# FMC_connector.net
KiCad netlist of a schematic drawn in Altium Designer
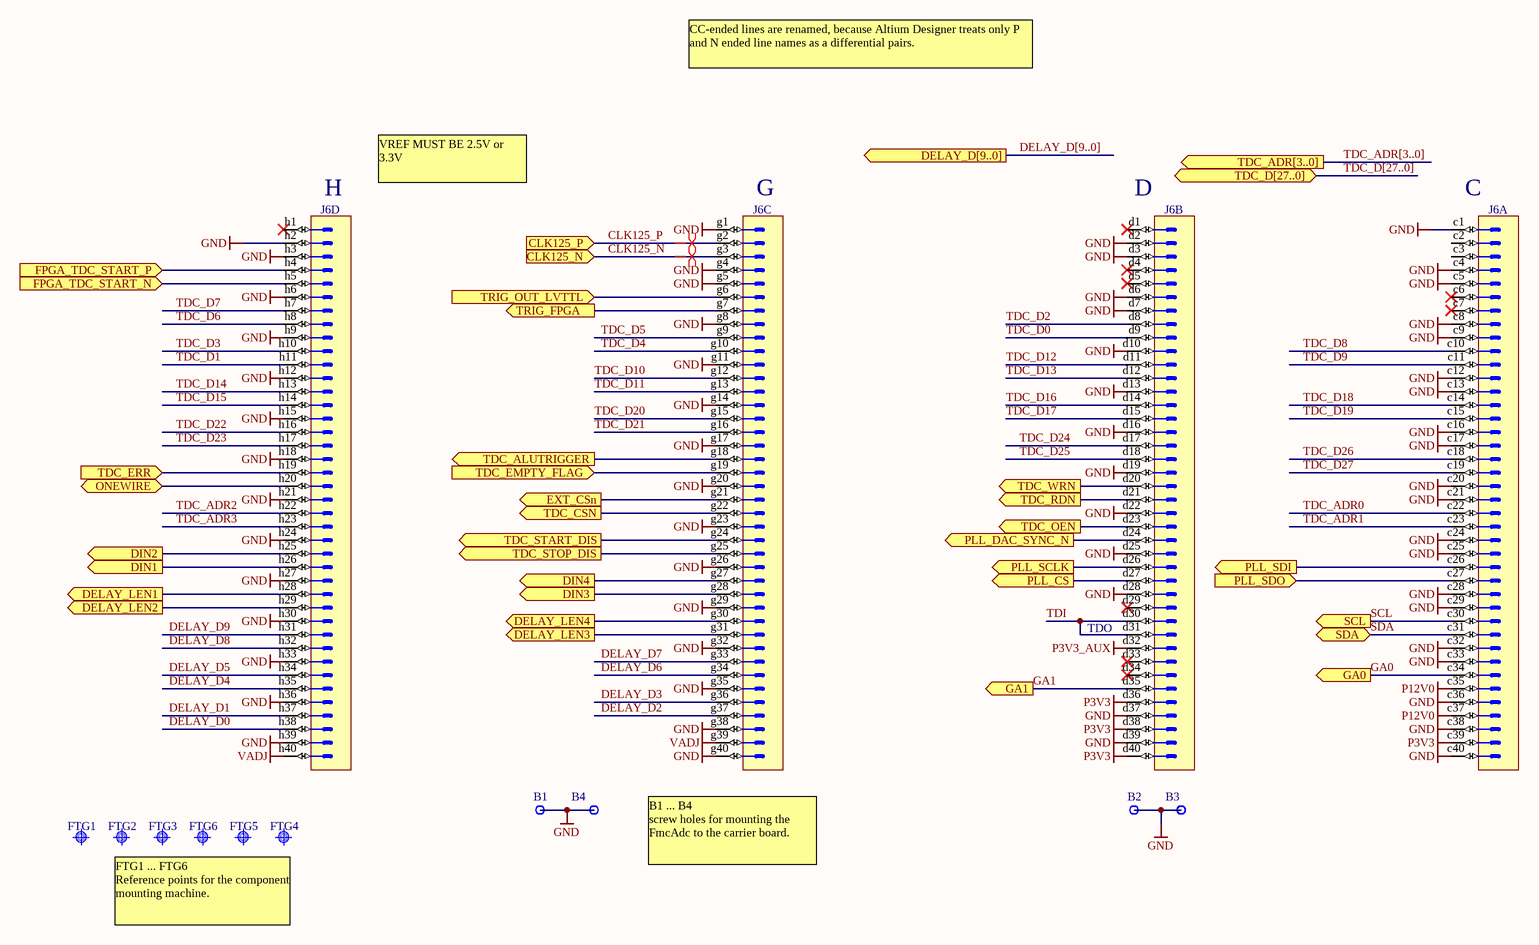
[diagram p0: FMC connector.SchDoc]

(export (version "E")
  (design (tool "Eeschema 10.0.6"))
  (components
    (comp (ref "B1")
      (value "Plated Hole")
      (footprint "MTG300_600")
      (description "Single Terminal Socket")
      (fields (field (name "PART NUMBER") "PLATED_HOLE3.0_PAD6.0") (field (name "AUTHOR") "CERN DEM JLC"))
      (libsource (lib "Eletro-mechanical") (part "Single Terminal Socket"))
    )
    (comp (ref "B2")
      (value "Plated Hole")
      (footprint "MTG300_600")
      (description "Single Terminal Socket")
      (fields (field (name "PART NUMBER") "PLATED_HOLE3.0_PAD6.0") (field (name "AUTHOR") "CERN DEM JLC"))
      (libsource (lib "Eletro-mechanical") (part "Single Terminal Socket"))
    )
    (comp (ref "B3")
      (value "Plated Hole")
      (footprint "MTG300_600")
      (description "Single Terminal Socket")
      (fields (field (name "PART NUMBER") "PLATED_HOLE3.0_PAD6.0") (field (name "AUTHOR") "CERN DEM JLC"))
      (libsource (lib "Eletro-mechanical") (part "Single Terminal Socket"))
    )
    (comp (ref "B4")
      (value "Plated Hole")
      (footprint "MTG300_600")
      (description "Single Terminal Socket")
      (fields (field (name "PART NUMBER") "PLATED_HOLE3.0_PAD6.0") (field (name "AUTHOR") "CERN DEM JLC"))
      (libsource (lib "Eletro-mechanical") (part "Single Terminal Socket"))
    )
    (comp (ref "FTG1")
      (value "Use only in PCB")
      (footprint "FIDUCIAL_TOP_S100-200")
      (description "Fiducial Target")
      (fields (field (name "PART NUMBER") "FIDUCIAL_TARGET_S100-200") (field (name "AUTHOR") "CERN DEM JLC"))
      (libsource (lib "Eletro-mechanical") (part "Fiducial Target"))
    )
    (comp (ref "FTG2")
      (value "Use only in PCB")
      (footprint "FIDUCIAL_TOP_S100-200")
      (description "Fiducial Target")
      (fields (field (name "PART NUMBER") "FIDUCIAL_TARGET_S100-200") (field (name "AUTHOR") "CERN DEM JLC"))
      (libsource (lib "Eletro-mechanical") (part "Fiducial Target"))
    )
    (comp (ref "FTG3")
      (value "Use only in PCB")
      (footprint "FIDUCIAL_TOP_S100-200")
      (description "Fiducial Target")
      (fields (field (name "PART NUMBER") "FIDUCIAL_TARGET_S100-200") (field (name "AUTHOR") "CERN DEM JLC"))
      (libsource (lib "Eletro-mechanical") (part "Fiducial Target"))
    )
    (comp (ref "FTG4")
      (value "Use only in PCB")
      (footprint "FIDUCIAL_TOP_S100-200")
      (description "Fiducial Target")
      (fields (field (name "PART NUMBER") "FIDUCIAL_TARGET_S100-200") (field (name "AUTHOR") "CERN DEM JLC"))
      (libsource (lib "Eletro-mechanical") (part "Fiducial Target"))
    )
    (comp (ref "FTG5")
      (value "Use only in PCB")
      (footprint "FIDUCIAL_TOP_S100-200")
      (description "Fiducial Target")
      (fields (field (name "PART NUMBER") "FIDUCIAL_TARGET_S100-200") (field (name "AUTHOR") "CERN DEM JLC"))
      (libsource (lib "Eletro-mechanical") (part "Fiducial Target"))
    )
    (comp (ref "FTG6")
      (value "Use only in PCB")
      (footprint "FIDUCIAL_TOP_S100-200")
      (description "Fiducial Target")
      (fields (field (name "PART NUMBER") "FIDUCIAL_TARGET_S100-200") (field (name "AUTHOR") "CERN DEM JLC"))
      (libsource (lib "Eletro-mechanical") (part "Fiducial Target"))
    )
    (comp (ref "J6")
      (value "VITA 57")
      (footprint "SAMTEC_ASP-127797-01")
      (description "Connector VITA 57, 160 Male contacts in 4 row cdgh")
      (fields
        (field (name "PART NUMBER") "SAMTEC_ASP-127797-01")
        (field (name "MANUFACTURER") "SAMTEC")
        (field (name "AUTHOR") "CERN DEM JLC")
      )
      (libsource (lib "Connectors") (part "Connector VITA 57 160 Male (cdgh)"))
    )
  )
  (nets
    (net (code "1") (name "/CLK125_N") (class "Default")
      (node (ref "J6") (pin "g3") (pinfunction "g3_g3") (pintype "bidirectional"))
    )
    (net (code "2") (name "/CLK125_P") (class "Default")
      (node (ref "J6") (pin "g2") (pinfunction "g2_g2") (pintype "bidirectional"))
    )
    (net (code "3") (name "/DELAY_D0") (class "Default")
      (node (ref "J6") (pin "h38") (pinfunction "h38_h38") (pintype "bidirectional"))
    )
    (net (code "4") (name "/DELAY_D1") (class "Default")
      (node (ref "J6") (pin "h37") (pinfunction "h37_h37") (pintype "bidirectional"))
    )
    (net (code "5") (name "/DELAY_D2") (class "Default")
      (node (ref "J6") (pin "g37") (pinfunction "g37_g37") (pintype "bidirectional"))
    )
    (net (code "6") (name "/DELAY_D3") (class "Default")
      (node (ref "J6") (pin "g36") (pinfunction "g36_g36") (pintype "bidirectional"))
    )
    (net (code "7") (name "/DELAY_D4") (class "Default")
      (node (ref "J6") (pin "h35") (pinfunction "h35_h35") (pintype "bidirectional"))
    )
    (net (code "8") (name "/DELAY_D5") (class "Default")
      (node (ref "J6") (pin "h34") (pinfunction "h34_h34") (pintype "bidirectional"))
    )
    (net (code "9") (name "/DELAY_D6") (class "Default")
      (node (ref "J6") (pin "g34") (pinfunction "g34_g34") (pintype "bidirectional"))
    )
    (net (code "10") (name "/DELAY_D7") (class "Default")
      (node (ref "J6") (pin "g33") (pinfunction "g33_g33") (pintype "bidirectional"))
    )
    (net (code "11") (name "/DELAY_D8") (class "Default")
      (node (ref "J6") (pin "h32") (pinfunction "h32_h32") (pintype "bidirectional"))
    )
    (net (code "12") (name "/DELAY_D9") (class "Default")
      (node (ref "J6") (pin "h31") (pinfunction "h31_h31") (pintype "bidirectional"))
    )
    (net (code "14") (name "/DELAY_LEN1") (class "Default")
      (node (ref "J6") (pin "h28") (pinfunction "h28_h28") (pintype "bidirectional"))
    )
    (net (code "15") (name "/DELAY_LEN2") (class "Default")
      (node (ref "J6") (pin "h29") (pinfunction "h29_h29") (pintype "bidirectional"))
    )
    (net (code "16") (name "/DELAY_LEN3") (class "Default")
      (node (ref "J6") (pin "g31") (pinfunction "g31_g31") (pintype "bidirectional"))
    )
    (net (code "17") (name "/DELAY_LEN4") (class "Default")
      (node (ref "J6") (pin "g30") (pinfunction "g30_g30") (pintype "bidirectional"))
    )
    (net (code "18") (name "/DIN1") (class "Default")
      (node (ref "J6") (pin "h26") (pinfunction "h26_h26") (pintype "bidirectional"))
    )
    (net (code "19") (name "/DIN2") (class "Default")
      (node (ref "J6") (pin "h25") (pinfunction "h25_h25") (pintype "bidirectional"))
    )
    (net (code "20") (name "/DIN3") (class "Default")
      (node (ref "J6") (pin "g28") (pinfunction "g28_g28") (pintype "bidirectional"))
    )
    (net (code "21") (name "/DIN4") (class "Default")
      (node (ref "J6") (pin "g27") (pinfunction "g27_g27") (pintype "bidirectional"))
    )
    (net (code "22") (name "/EXT_CSn") (class "Default")
      (node (ref "J6") (pin "g21") (pinfunction "g21_g21") (pintype "bidirectional"))
    )
    (net (code "23") (name "/FPGA_TDC_START_N") (class "Default")
      (node (ref "J6") (pin "h5") (pinfunction "h5_h5") (pintype "bidirectional"))
    )
    (net (code "24") (name "/FPGA_TDC_START_P") (class "Default")
      (node (ref "J6") (pin "h4") (pinfunction "h4_h4") (pintype "bidirectional"))
    )
    (net (code "25") (name "/GA0") (class "Default")
      (node (ref "J6") (pin "c34") (pinfunction "c34_c34") (pintype "bidirectional"))
    )
    (net (code "26") (name "/GA1") (class "Default")
      (node (ref "J6") (pin "d35") (pinfunction "d35_d35") (pintype "bidirectional"))
    )
    (net (code "27") (name "/ONEWIRE") (class "Default")
      (node (ref "J6") (pin "h20") (pinfunction "h20_h20") (pintype "bidirectional"))
    )
    (net (code "28") (name "/PLL_CS") (class "Default")
      (node (ref "J6") (pin "d27") (pinfunction "d27_d27") (pintype "bidirectional"))
    )
    (net (code "29") (name "/PLL_DAC_SYNC_N") (class "Default")
      (node (ref "J6") (pin "d24") (pinfunction "d24_d24") (pintype "bidirectional"))
    )
    (net (code "30") (name "/PLL_SCLK") (class "Default")
      (node (ref "J6") (pin "d26") (pinfunction "d26_d26") (pintype "bidirectional"))
    )
    (net (code "31") (name "/PLL_SDI") (class "Default")
      (node (ref "J6") (pin "c26") (pinfunction "c26_c26") (pintype "bidirectional"))
    )
    (net (code "32") (name "/PLL_SDO") (class "Default")
      (node (ref "J6") (pin "c27") (pinfunction "c27_c27") (pintype "bidirectional"))
    )
    (net (code "33") (name "/SCL") (class "Default")
      (node (ref "J6") (pin "c30") (pinfunction "c30_c30") (pintype "bidirectional"))
    )
    (net (code "34") (name "/SDA") (class "Default")
      (node (ref "J6") (pin "c31") (pinfunction "c31_c31") (pintype "bidirectional"))
    )
    (net (code "35") (name "/TDC_ADR0") (class "Default")
      (node (ref "J6") (pin "c22") (pinfunction "c22_c22") (pintype "bidirectional"))
    )
    (net (code "36") (name "/TDC_ADR1") (class "Default")
      (node (ref "J6") (pin "c23") (pinfunction "c23_c23") (pintype "bidirectional"))
    )
    (net (code "37") (name "/TDC_ADR2") (class "Default")
      (node (ref "J6") (pin "h22") (pinfunction "h22_h22") (pintype "bidirectional"))
    )
    (net (code "38") (name "/TDC_ADR3") (class "Default")
      (node (ref "J6") (pin "h23") (pinfunction "h23_h23") (pintype "bidirectional"))
    )
    (net (code "40") (name "/TDC_ALUTRIGGER") (class "Default")
      (node (ref "J6") (pin "g18") (pinfunction "g18_g18") (pintype "bidirectional"))
    )
    (net (code "41") (name "/TDC_CSN") (class "Default")
      (node (ref "J6") (pin "g22") (pinfunction "g22_g22") (pintype "bidirectional"))
    )
    (net (code "42") (name "/TDC_D0") (class "Default")
      (node (ref "J6") (pin "d9") (pinfunction "d9_d9") (pintype "bidirectional"))
    )
    (net (code "43") (name "/TDC_D1") (class "Default")
      (node (ref "J6") (pin "h11") (pinfunction "h11_h11") (pintype "bidirectional"))
    )
    (net (code "44") (name "/TDC_D2") (class "Default")
      (node (ref "J6") (pin "d8") (pinfunction "d8_d8") (pintype "bidirectional"))
    )
    (net (code "45") (name "/TDC_D3") (class "Default")
      (node (ref "J6") (pin "h10") (pinfunction "h10_h10") (pintype "bidirectional"))
    )
    (net (code "46") (name "/TDC_D4") (class "Default")
      (node (ref "J6") (pin "g10") (pinfunction "g10_g10") (pintype "bidirectional"))
    )
    (net (code "47") (name "/TDC_D5") (class "Default")
      (node (ref "J6") (pin "g9") (pinfunction "g9_g9") (pintype "bidirectional"))
    )
    (net (code "48") (name "/TDC_D6") (class "Default")
      (node (ref "J6") (pin "h8") (pinfunction "h8_h8") (pintype "bidirectional"))
    )
    (net (code "49") (name "/TDC_D7") (class "Default")
      (node (ref "J6") (pin "h7") (pinfunction "h7_h7") (pintype "bidirectional"))
    )
    (net (code "50") (name "/TDC_D8") (class "Default")
      (node (ref "J6") (pin "c10") (pinfunction "c10_c10") (pintype "bidirectional"))
    )
    (net (code "51") (name "/TDC_D9") (class "Default")
      (node (ref "J6") (pin "c11") (pinfunction "c11_c11") (pintype "bidirectional"))
    )
    (net (code "52") (name "/TDC_D10") (class "Default")
      (node (ref "J6") (pin "g12") (pinfunction "g12_g12") (pintype "bidirectional"))
    )
    (net (code "53") (name "/TDC_D11") (class "Default")
      (node (ref "J6") (pin "g13") (pinfunction "g13_g13") (pintype "bidirectional"))
    )
    (net (code "54") (name "/TDC_D12") (class "Default")
      (node (ref "J6") (pin "d11") (pinfunction "d11_d11") (pintype "bidirectional"))
    )
    (net (code "55") (name "/TDC_D13") (class "Default")
      (node (ref "J6") (pin "d12") (pinfunction "d12_d12") (pintype "bidirectional"))
    )
    (net (code "56") (name "/TDC_D14") (class "Default")
      (node (ref "J6") (pin "h13") (pinfunction "h13_h13") (pintype "bidirectional"))
    )
    (net (code "57") (name "/TDC_D15") (class "Default")
      (node (ref "J6") (pin "h14") (pinfunction "h14_h14") (pintype "bidirectional"))
    )
    (net (code "58") (name "/TDC_D16") (class "Default")
      (node (ref "J6") (pin "d14") (pinfunction "d14_d14") (pintype "bidirectional"))
    )
    (net (code "59") (name "/TDC_D17") (class "Default")
      (node (ref "J6") (pin "d15") (pinfunction "d15_d15") (pintype "bidirectional"))
    )
    (net (code "60") (name "/TDC_D18") (class "Default")
      (node (ref "J6") (pin "c14") (pinfunction "c14_c14") (pintype "bidirectional"))
    )
    (net (code "61") (name "/TDC_D19") (class "Default")
      (node (ref "J6") (pin "c15") (pinfunction "c15_c15") (pintype "bidirectional"))
    )
    (net (code "62") (name "/TDC_D20") (class "Default")
      (node (ref "J6") (pin "g15") (pinfunction "g15_g15") (pintype "bidirectional"))
    )
    (net (code "63") (name "/TDC_D21") (class "Default")
      (node (ref "J6") (pin "g16") (pinfunction "g16_g16") (pintype "bidirectional"))
    )
    (net (code "64") (name "/TDC_D22") (class "Default")
      (node (ref "J6") (pin "h16") (pinfunction "h16_h16") (pintype "bidirectional"))
    )
    (net (code "65") (name "/TDC_D23") (class "Default")
      (node (ref "J6") (pin "h17") (pinfunction "h17_h17") (pintype "bidirectional"))
    )
    (net (code "66") (name "/TDC_D24") (class "Default")
      (node (ref "J6") (pin "d17") (pinfunction "d17_d17") (pintype "bidirectional"))
    )
    (net (code "67") (name "/TDC_D25") (class "Default")
      (node (ref "J6") (pin "d18") (pinfunction "d18_d18") (pintype "bidirectional"))
    )
    (net (code "68") (name "/TDC_D26") (class "Default")
      (node (ref "J6") (pin "c18") (pinfunction "c18_c18") (pintype "bidirectional"))
    )
    (net (code "69") (name "/TDC_D27") (class "Default")
      (node (ref "J6") (pin "c19") (pinfunction "c19_c19") (pintype "bidirectional"))
    )
    (net (code "71") (name "/TDC_EMPTY_FLAG") (class "Default")
      (node (ref "J6") (pin "g19") (pinfunction "g19_g19") (pintype "bidirectional"))
    )
    (net (code "72") (name "/TDC_ERR") (class "Default")
      (node (ref "J6") (pin "h19") (pinfunction "h19_h19") (pintype "bidirectional"))
    )
    (net (code "73") (name "/TDC_OEN") (class "Default")
      (node (ref "J6") (pin "d23") (pinfunction "d23_d23") (pintype "bidirectional"))
    )
    (net (code "74") (name "/TDC_RDN") (class "Default")
      (node (ref "J6") (pin "d21") (pinfunction "d21_d21") (pintype "bidirectional"))
    )
    (net (code "75") (name "/TDC_START_DIS") (class "Default")
      (node (ref "J6") (pin "g24") (pinfunction "g24_g24") (pintype "bidirectional"))
    )
    (net (code "76") (name "/TDC_STOP_DIS") (class "Default")
      (node (ref "J6") (pin "g25") (pinfunction "g25_g25") (pintype "bidirectional"))
    )
    (net (code "77") (name "/TDC_WRN") (class "Default")
      (node (ref "J6") (pin "d20") (pinfunction "d20_d20") (pintype "bidirectional"))
    )
    (net (code "78") (name "/TDI") (class "Default")
      (node (ref "J6") (pin "d30") (pinfunction "d30_d30") (pintype "bidirectional"))
      (node (ref "J6") (pin "d31") (pinfunction "d31_d31") (pintype "bidirectional"))
    )
    (net (code "79") (name "/TRIG_FPGA") (class "Default")
      (node (ref "J6") (pin "g7") (pinfunction "g7_g7") (pintype "bidirectional"))
    )
    (net (code "80") (name "/TRIG_OUT_LVTTL") (class "Default")
      (node (ref "J6") (pin "g6") (pinfunction "g6_g6") (pintype "bidirectional"))
    )
    (net (code "81") (name "GND") (class "Default")
      (node (ref "B1") (pin "1") (pinfunction "1_1") (pintype "bidirectional"))
      (node (ref "B2") (pin "1") (pinfunction "1_1") (pintype "bidirectional"))
      (node (ref "B3") (pin "1") (pinfunction "1_1") (pintype "bidirectional"))
      (node (ref "B4") (pin "1") (pinfunction "1_1") (pintype "bidirectional"))
      (node (ref "J6") (pin "c1") (pinfunction "c1_c1") (pintype "bidirectional"))
      (node (ref "J6") (pin "c12") (pinfunction "c12_c12") (pintype "bidirectional"))
      (node (ref "J6") (pin "c13") (pinfunction "c13_c13") (pintype "bidirectional"))
      (node (ref "J6") (pin "c16") (pinfunction "c16_c16") (pintype "bidirectional"))
      (node (ref "J6") (pin "c17") (pinfunction "c17_c17") (pintype "bidirectional"))
      (node (ref "J6") (pin "c20") (pinfunction "c20_c20") (pintype "bidirectional"))
      (node (ref "J6") (pin "c21") (pinfunction "c21_c21") (pintype "bidirectional"))
      (node (ref "J6") (pin "c24") (pinfunction "c24_c24") (pintype "bidirectional"))
      (node (ref "J6") (pin "c25") (pinfunction "c25_c25") (pintype "bidirectional"))
      (node (ref "J6") (pin "c28") (pinfunction "c28_c28") (pintype "bidirectional"))
      (node (ref "J6") (pin "c29") (pinfunction "c29_c29") (pintype "bidirectional"))
      (node (ref "J6") (pin "c32") (pinfunction "c32_c32") (pintype "bidirectional"))
      (node (ref "J6") (pin "c33") (pinfunction "c33_c33") (pintype "bidirectional"))
      (node (ref "J6") (pin "c36") (pinfunction "c36_c36") (pintype "bidirectional"))
      (node (ref "J6") (pin "c38") (pinfunction "c38_c38") (pintype "bidirectional"))
      (node (ref "J6") (pin "c4") (pinfunction "c4_c4") (pintype "bidirectional"))
      (node (ref "J6") (pin "c40") (pinfunction "c40_c40") (pintype "bidirectional"))
      (node (ref "J6") (pin "c5") (pinfunction "c5_c5") (pintype "bidirectional"))
      (node (ref "J6") (pin "c8") (pinfunction "c8_c8") (pintype "bidirectional"))
      (node (ref "J6") (pin "c9") (pinfunction "c9_c9") (pintype "bidirectional"))
      (node (ref "J6") (pin "d10") (pinfunction "d10_d10") (pintype "bidirectional"))
      (node (ref "J6") (pin "d13") (pinfunction "d13_d13") (pintype "bidirectional"))
      (node (ref "J6") (pin "d16") (pinfunction "d16_d16") (pintype "bidirectional"))
      (node (ref "J6") (pin "d19") (pinfunction "d19_d19") (pintype "bidirectional"))
      (node (ref "J6") (pin "d2") (pinfunction "d2_d2") (pintype "bidirectional"))
      (node (ref "J6") (pin "d22") (pinfunction "d22_d22") (pintype "bidirectional"))
      (node (ref "J6") (pin "d25") (pinfunction "d25_d25") (pintype "bidirectional"))
      (node (ref "J6") (pin "d28") (pinfunction "d28_d28") (pintype "bidirectional"))
      (node (ref "J6") (pin "d3") (pinfunction "d3_d3") (pintype "bidirectional"))
      (node (ref "J6") (pin "d37") (pinfunction "d37_d37") (pintype "bidirectional"))
      (node (ref "J6") (pin "d39") (pinfunction "d39_d39") (pintype "bidirectional"))
      (node (ref "J6") (pin "d6") (pinfunction "d6_d6") (pintype "bidirectional"))
      (node (ref "J6") (pin "d7") (pinfunction "d7_d7") (pintype "bidirectional"))
      (node (ref "J6") (pin "g1") (pinfunction "g1_g1") (pintype "bidirectional"))
      (node (ref "J6") (pin "g11") (pinfunction "g11_g11") (pintype "bidirectional"))
      (node (ref "J6") (pin "g14") (pinfunction "g14_g14") (pintype "bidirectional"))
      (node (ref "J6") (pin "g17") (pinfunction "g17_g17") (pintype "bidirectional"))
      (node (ref "J6") (pin "g20") (pinfunction "g20_g20") (pintype "bidirectional"))
      (node (ref "J6") (pin "g23") (pinfunction "g23_g23") (pintype "bidirectional"))
      (node (ref "J6") (pin "g26") (pinfunction "g26_g26") (pintype "bidirectional"))
      (node (ref "J6") (pin "g29") (pinfunction "g29_g29") (pintype "bidirectional"))
      (node (ref "J6") (pin "g32") (pinfunction "g32_g32") (pintype "bidirectional"))
      (node (ref "J6") (pin "g35") (pinfunction "g35_g35") (pintype "bidirectional"))
      (node (ref "J6") (pin "g38") (pinfunction "g38_g38") (pintype "bidirectional"))
      (node (ref "J6") (pin "g4") (pinfunction "g4_g4") (pintype "bidirectional"))
      (node (ref "J6") (pin "g40") (pinfunction "g40_g40") (pintype "bidirectional"))
      (node (ref "J6") (pin "g5") (pinfunction "g5_g5") (pintype "bidirectional"))
      (node (ref "J6") (pin "g8") (pinfunction "g8_g8") (pintype "bidirectional"))
      (node (ref "J6") (pin "h12") (pinfunction "h12_h12") (pintype "bidirectional"))
      (node (ref "J6") (pin "h15") (pinfunction "h15_h15") (pintype "bidirectional"))
      (node (ref "J6") (pin "h18") (pinfunction "h18_h18") (pintype "bidirectional"))
      (node (ref "J6") (pin "h2") (pinfunction "h2_h2") (pintype "bidirectional"))
      (node (ref "J6") (pin "h21") (pinfunction "h21_h21") (pintype "bidirectional"))
      (node (ref "J6") (pin "h24") (pinfunction "h24_h24") (pintype "bidirectional"))
      (node (ref "J6") (pin "h27") (pinfunction "h27_h27") (pintype "bidirectional"))
      (node (ref "J6") (pin "h3") (pinfunction "h3_h3") (pintype "bidirectional"))
      (node (ref "J6") (pin "h30") (pinfunction "h30_h30") (pintype "bidirectional"))
      (node (ref "J6") (pin "h33") (pinfunction "h33_h33") (pintype "bidirectional"))
      (node (ref "J6") (pin "h36") (pinfunction "h36_h36") (pintype "bidirectional"))
      (node (ref "J6") (pin "h39") (pinfunction "h39_h39") (pintype "bidirectional"))
      (node (ref "J6") (pin "h6") (pinfunction "h6_h6") (pintype "bidirectional"))
      (node (ref "J6") (pin "h9") (pinfunction "h9_h9") (pintype "bidirectional"))
    )
    (net (code "82") (name "P3V3") (class "Default")
      (node (ref "J6") (pin "c39") (pinfunction "c39_c39") (pintype "bidirectional"))
      (node (ref "J6") (pin "d36") (pinfunction "d36_d36") (pintype "bidirectional"))
      (node (ref "J6") (pin "d38") (pinfunction "d38_d38") (pintype "bidirectional"))
      (node (ref "J6") (pin "d40") (pinfunction "d40_d40") (pintype "bidirectional"))
    )
    (net (code "83") (name "P3V3_AUX") (class "Default")
      (node (ref "J6") (pin "d32") (pinfunction "d32_d32") (pintype "bidirectional"))
    )
    (net (code "84") (name "P12V0") (class "Default")
      (node (ref "J6") (pin "c35") (pinfunction "c35_c35") (pintype "bidirectional"))
      (node (ref "J6") (pin "c37") (pinfunction "c37_c37") (pintype "bidirectional"))
    )
    (net (code "85") (name "VADJ") (class "Default")
      (node (ref "J6") (pin "g39") (pinfunction "g39_g39") (pintype "bidirectional"))
      (node (ref "J6") (pin "h40") (pinfunction "h40_h40") (pintype "bidirectional"))
    )
    (net (code "86") (name "unconnected-(J6-Padc2)") (class "Default")
      (node (ref "J6") (pin "c2") (pinfunction "c2_c2") (pintype "bidirectional"))
    )
    (net (code "87") (name "unconnected-(J6-Padc3)") (class "Default")
      (node (ref "J6") (pin "c3") (pinfunction "c3_c3") (pintype "bidirectional"))
    )
    (net (code "88") (name "unconnected-(J6-Padc6)") (class "Default")
      (node (ref "J6") (pin "c6") (pinfunction "c6_c6") (pintype "bidirectional+no_connect"))
    )
    (net (code "89") (name "unconnected-(J6-Padc7)") (class "Default")
      (node (ref "J6") (pin "c7") (pinfunction "c7_c7") (pintype "bidirectional+no_connect"))
    )
    (net (code "90") (name "unconnected-(J6-Padd1)") (class "Default")
      (node (ref "J6") (pin "d1") (pinfunction "d1_d1") (pintype "bidirectional+no_connect"))
    )
    (net (code "91") (name "unconnected-(J6-Padd4)") (class "Default")
      (node (ref "J6") (pin "d4") (pinfunction "d4_d4") (pintype "bidirectional+no_connect"))
    )
    (net (code "92") (name "unconnected-(J6-Padd5)") (class "Default")
      (node (ref "J6") (pin "d5") (pinfunction "d5_d5") (pintype "bidirectional+no_connect"))
    )
    (net (code "93") (name "unconnected-(J6-Padd29)") (class "Default")
      (node (ref "J6") (pin "d29") (pinfunction "d29_d29") (pintype "bidirectional+no_connect"))
    )
    (net (code "94") (name "unconnected-(J6-Padd33)") (class "Default")
      (node (ref "J6") (pin "d33") (pinfunction "d33_d33") (pintype "bidirectional+no_connect"))
    )
    (net (code "95") (name "unconnected-(J6-Padd34)") (class "Default")
      (node (ref "J6") (pin "d34") (pinfunction "d34_d34") (pintype "bidirectional+no_connect"))
    )
    (net (code "96") (name "unconnected-(J6-Padh1)") (class "Default")
      (node (ref "J6") (pin "h1") (pinfunction "h1_h1") (pintype "bidirectional+no_connect"))
    )
  )
)
